# board.net
KiCad netlist of a schematic drawn in EAGLE
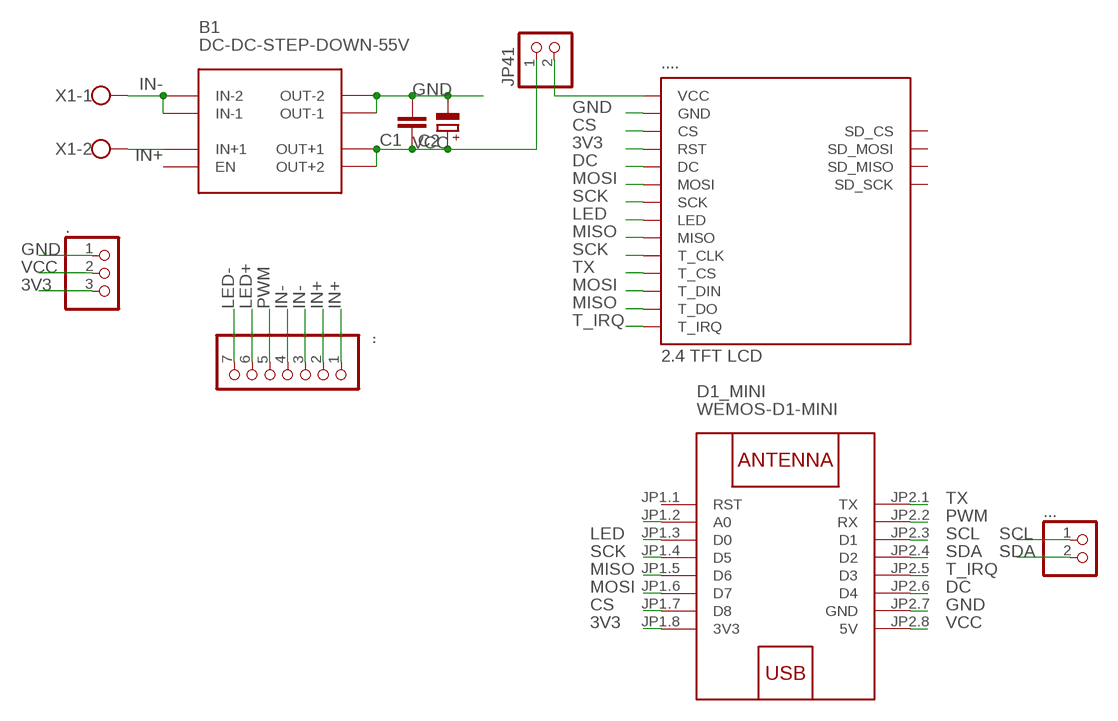
[diagram p0: schematic, sheet 1]

(export (version "E")
  (design (tool "Eeschema 10.0.6"))
  (components
    (comp (ref ".")
      (value "PINHD-1X3")
      (footprint "eagle-import:1X03")
      (libsource (lib "eagle-import") (part "PINHD-1X3"))
    )
    (comp (ref "..")
      (value "PINHD-1X7")
      (footprint "eagle-import:1X07")
      (libsource (lib "eagle-import") (part "PINHD-1X7"))
    )
    (comp (ref "...")
      (value "PINHD-1X2")
      (footprint "eagle-import:1X02")
      (libsource (lib "eagle-import") (part "PINHD-1X2"))
    )
    (comp (ref "....")
      (value "2.2_TFT_LCD")
      (footprint "eagle-import:2.2_TFT_LCD")
      (libsource (lib "eagle-import") (part "2.2_TFT_LCD"))
    )
    (comp (ref "B1")
      (value "DC-DC-STEP-DOWN-55V")
      (footprint "eagle-import:DC-DC-STEP-DOWN-55V")
      (libsource (lib "eagle-import") (part "DC-DC-STEP-DOWN-55V"))
    )
    (comp (ref "C1")
      (value "C-EUC0805")
      (footprint "eagle-import:C0805")
      (libsource (lib "eagle-import") (part "C-EUC0805"))
    )
    (comp (ref "C2")
      (value "CPOL-EUE2-5")
      (footprint "eagle-import:E2-5")
      (libsource (lib "eagle-import") (part "CPOL-EUE2-5"))
    )
    (comp (ref "D1_MINI")
      (value "WEMOS-D1-MINI")
      (footprint "eagle-import:WEMOS-D1-MINI")
      (libsource (lib "eagle-import") (part "WEMOS-D1-MINI"))
    )
    (comp (ref "JP41")
      (value "PINHD-1X2")
      (footprint "eagle-import:1X02")
      (libsource (lib "eagle-import") (part "PINHD-1X2"))
    )
    (comp (ref "X1")
      (value "W237-102")
      (footprint "eagle-import:W237-102")
      (fields (field (name "MPN") "237-102"))
      (libsource (lib "eagle-import") (part "W237-102"))
    )
  )
  (nets
    (net (code "1") (name "/3V3") (class "Default")
      (node (ref ".") (pin "3") (pinfunction "3_3") (pintype "passive"))
      (node (ref "....") (pin "RST") (pinfunction "RST_RST") (pintype "bidirectional"))
      (node (ref "D1_MINI") (pin "JP1.8") (pinfunction "3V3_JP1.8") (pintype "power_in"))
    )
    (net (code "2") (name "/CS") (class "Default")
      (node (ref "....") (pin "CS") (pinfunction "CS_CS") (pintype "bidirectional"))
      (node (ref "D1_MINI") (pin "JP1.7") (pinfunction "D8_JP1.7") (pintype "bidirectional"))
    )
    (net (code "3") (name "/DC") (class "Default")
      (node (ref "....") (pin "DC") (pinfunction "DC_DC") (pintype "bidirectional"))
      (node (ref "D1_MINI") (pin "JP2.6") (pinfunction "D4_JP2.6") (pintype "bidirectional"))
    )
    (net (code "4") (name "/GND") (class "Default")
      (node (ref ".") (pin "1") (pinfunction "1_1") (pintype "passive"))
      (node (ref "....") (pin "GND") (pinfunction "GND_GND") (pintype "power_in"))
      (node (ref "B1") (pin "VOUT-1") (pinfunction "OUT-1_VOUT-1") (pintype "bidirectional"))
      (node (ref "B1") (pin "VOUT-2") (pinfunction "OUT-2_VOUT-2") (pintype "bidirectional"))
      (node (ref "C1") (pin "2") (pinfunction "2_2") (pintype "passive"))
      (node (ref "C2") (pin "-") (pinfunction "-_-") (pintype "passive"))
      (node (ref "D1_MINI") (pin "JP2.7") (pinfunction "GND_JP2.7") (pintype "power_in"))
    )
    (net (code "5") (name "/IN+") (class "Default")
      (node (ref "..") (pin "1") (pinfunction "1_1") (pintype "passive"))
      (node (ref "..") (pin "2") (pinfunction "2_2") (pintype "passive"))
      (node (ref "B1") (pin "VIN+") (pinfunction "IN+1_VIN+") (pintype "bidirectional"))
      (node (ref "X1") (pin "2") (pinfunction "KL_2") (pintype "passive"))
    )
    (net (code "6") (name "/IN-") (class "Default")
      (node (ref "..") (pin "3") (pinfunction "3_3") (pintype "passive"))
      (node (ref "..") (pin "4") (pinfunction "4_4") (pintype "passive"))
      (node (ref "B1") (pin "VIN-1") (pinfunction "IN-1_VIN-1") (pintype "bidirectional"))
      (node (ref "B1") (pin "VIN-2") (pinfunction "IN-2_VIN-2") (pintype "bidirectional"))
      (node (ref "X1") (pin "1") (pinfunction "KL_1") (pintype "passive"))
    )
    (net (code "7") (name "/LED") (class "Default")
      (node (ref "....") (pin "LED") (pinfunction "LED_LED") (pintype "bidirectional"))
      (node (ref "D1_MINI") (pin "JP1.3") (pinfunction "D0_JP1.3") (pintype "bidirectional"))
    )
    (net (code "8") (name "/LED+") (class "Default")
      (node (ref "..") (pin "6") (pinfunction "6_6") (pintype "passive"))
    )
    (net (code "9") (name "/LED-") (class "Default")
      (node (ref "..") (pin "7") (pinfunction "7_7") (pintype "passive"))
    )
    (net (code "10") (name "/MISO") (class "Default")
      (node (ref "....") (pin "MISO") (pinfunction "MISO_MISO") (pintype "bidirectional"))
      (node (ref "....") (pin "T_DO") (pinfunction "T_DO_T_DO") (pintype "bidirectional"))
      (node (ref "D1_MINI") (pin "JP1.5") (pinfunction "D6_JP1.5") (pintype "bidirectional"))
    )
    (net (code "11") (name "/MOSI") (class "Default")
      (node (ref "....") (pin "MOSI") (pinfunction "MOSI_MOSI") (pintype "bidirectional"))
      (node (ref "....") (pin "T_DIN") (pinfunction "T_DIN_T_DIN") (pintype "bidirectional"))
      (node (ref "D1_MINI") (pin "JP1.6") (pinfunction "D7_JP1.6") (pintype "bidirectional"))
    )
    (net (code "12") (name "/PWM") (class "Default")
      (node (ref "..") (pin "5") (pinfunction "5_5") (pintype "passive"))
      (node (ref "D1_MINI") (pin "JP2.2") (pinfunction "RX_JP2.2") (pintype "bidirectional"))
    )
    (net (code "13") (name "/SCK") (class "Default")
      (node (ref "....") (pin "SCK") (pinfunction "SCK_SCK") (pintype "bidirectional"))
      (node (ref "....") (pin "T_CLK") (pinfunction "T_CLK_T_CLK") (pintype "bidirectional"))
      (node (ref "D1_MINI") (pin "JP1.4") (pinfunction "D5_JP1.4") (pintype "bidirectional"))
    )
    (net (code "14") (name "/SCL") (class "Default")
      (node (ref "...") (pin "1") (pinfunction "1_1") (pintype "passive"))
      (node (ref "D1_MINI") (pin "JP2.3") (pinfunction "D1_JP2.3") (pintype "bidirectional"))
    )
    (net (code "15") (name "/SDA") (class "Default")
      (node (ref "...") (pin "2") (pinfunction "2_2") (pintype "passive"))
      (node (ref "D1_MINI") (pin "JP2.4") (pinfunction "D2_JP2.4") (pintype "bidirectional"))
    )
    (net (code "16") (name "/TX") (class "Default")
      (node (ref "....") (pin "T_CS") (pinfunction "T_CS_T_CS") (pintype "bidirectional"))
      (node (ref "D1_MINI") (pin "JP2.1") (pinfunction "TX_JP2.1") (pintype "bidirectional"))
    )
    (net (code "17") (name "/T_IRQ") (class "Default")
      (node (ref "....") (pin "T_IRQ") (pinfunction "T_IRQ_T_IRQ") (pintype "bidirectional"))
      (node (ref "D1_MINI") (pin "JP2.5") (pinfunction "D3_JP2.5") (pintype "bidirectional"))
    )
    (net (code "18") (name "/VCC") (class "Default")
      (node (ref ".") (pin "2") (pinfunction "2_2") (pintype "passive"))
      (node (ref "B1") (pin "VOUT+1") (pinfunction "OUT+1_VOUT+1") (pintype "bidirectional"))
      (node (ref "B1") (pin "VOUT+2") (pinfunction "OUT+2_VOUT+2") (pintype "bidirectional"))
      (node (ref "C1") (pin "1") (pinfunction "1_1") (pintype "passive"))
      (node (ref "C2") (pin "+") (pinfunction "+_+") (pintype "passive"))
      (node (ref "D1_MINI") (pin "JP2.8") (pinfunction "5V_JP2.8") (pintype "power_in"))
      (node (ref "JP41") (pin "1") (pinfunction "1_1") (pintype "passive"))
    )
    (net (code "19") (name "Net-(....-PadVCC)") (class "Default")
      (node (ref "....") (pin "VCC") (pinfunction "VCC_VCC") (pintype "power_in"))
      (node (ref "JP41") (pin "2") (pinfunction "2_2") (pintype "passive"))
    )
    (net (code "20") (name "unconnected-(....-PadSD_CS)") (class "Default")
      (node (ref "....") (pin "SD_CS") (pinfunction "SD_CS_SD_CS") (pintype "bidirectional"))
    )
    (net (code "21") (name "unconnected-(....-PadSD_MISO)") (class "Default")
      (node (ref "....") (pin "SD_MISO") (pinfunction "SD_MISO_SD_MISO") (pintype "bidirectional"))
    )
    (net (code "22") (name "unconnected-(....-PadSD_MOSI)") (class "Default")
      (node (ref "....") (pin "SD_MOSI") (pinfunction "SD_MOSI_SD_MOSI") (pintype "bidirectional"))
    )
    (net (code "23") (name "unconnected-(....-PadSD_SCK)") (class "Default")
      (node (ref "....") (pin "SD_SCK") (pinfunction "SD_SCK_SD_SCK") (pintype "bidirectional"))
    )
    (net (code "24") (name "unconnected-(B1-PadEN)") (class "Default")
      (node (ref "B1") (pin "EN") (pinfunction "EN_EN") (pintype "bidirectional"))
    )
    (net (code "25") (name "unconnected-(D1_MINI-A0-PadJP1.2)") (class "Default")
      (node (ref "D1_MINI") (pin "JP1.2") (pinfunction "A0_JP1.2") (pintype "bidirectional"))
    )
    (net (code "26") (name "unconnected-(D1_MINI-RST-PadJP1.1)") (class "Default")
      (node (ref "D1_MINI") (pin "JP1.1") (pinfunction "RST_JP1.1") (pintype "bidirectional"))
    )
  )
)
